# FSWSJE2IZ6BVKJ2.net
KiCad netlist of a schematic drawn in EAGLE
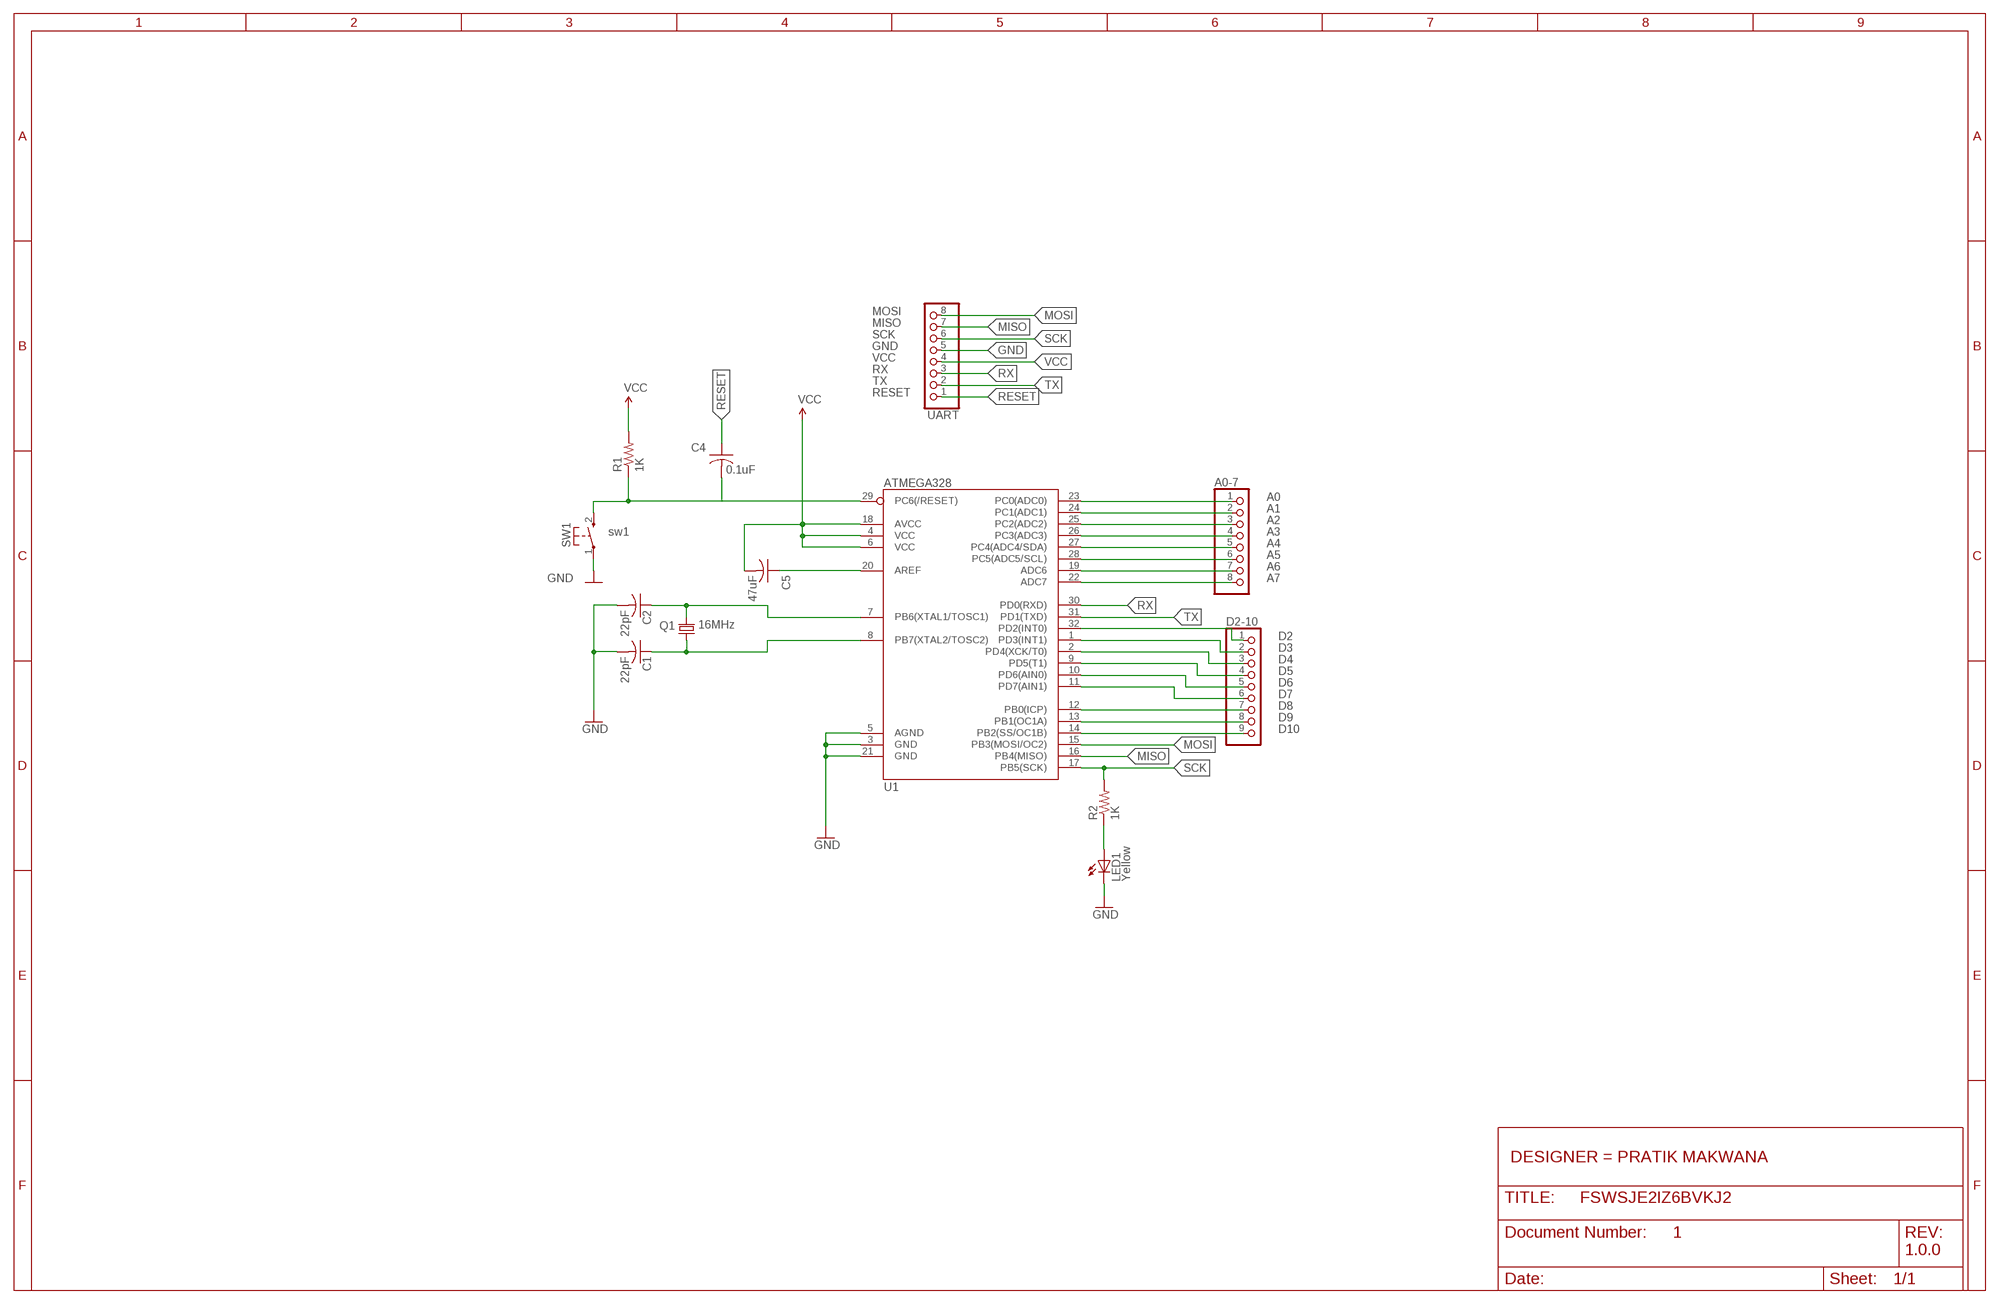
[diagram p0: schematic, sheet 1]

(export (version "E")
  (design (tool "Eeschema 10.0.6"))
  (components
    (comp (ref "A0-7")
      (value "PINHD-1X8CLEANBIG")
      (footprint "eagle-import:1X08-CLEANBIG")
      (libsource (lib "eagle-import") (part "PINHD-1X8CLEANBIG"))
    )
    (comp (ref "C1")
      (value "22pF")
      (footprint "eagle-import:C1206")
      (libsource (lib "eagle-import") (part "C-USC1206"))
    )
    (comp (ref "C2")
      (value "22pF")
      (footprint "eagle-import:C1206")
      (libsource (lib "eagle-import") (part "C-USC1206"))
    )
    (comp (ref "C4")
      (value "0.1uF")
      (footprint "eagle-import:C0805")
      (libsource (lib "eagle-import") (part "C-USC0805"))
    )
    (comp (ref "C5")
      (value "47uF")
      (footprint "eagle-import:C0805")
      (libsource (lib "eagle-import") (part "C-USC0805"))
    )
    (comp (ref "D2-10")
      (value "PINHD-1X9")
      (footprint "eagle-import:1X09-BIG")
      (libsource (lib "eagle-import") (part "PINHD-1X9"))
    )
    (comp (ref "LED1")
      (value "Yellow")
      (footprint "eagle-import:CHIP-LED0805")
      (libsource (lib "eagle-import") (part "LEDCHIP-LED0805"))
    )
    (comp (ref "Q1")
      (value "16MHz")
      (footprint "eagle-import:HC49_S")
      (libsource (lib "eagle-import") (part "CRYTALHC49S"))
    )
    (comp (ref "R1")
      (value "1K")
      (footprint "eagle-import:R1206")
      (libsource (lib "eagle-import") (part "R-US_R1206"))
    )
    (comp (ref "R2")
      (value "1K")
      (footprint "eagle-import:R1206")
      (libsource (lib "eagle-import") (part "R-US_R1206"))
    )
    (comp (ref "SW1")
      (value "sw1")
      (footprint "eagle-import:KSS-2EG4430")
      (libsource (lib "eagle-import") (part "KSS-2EG4430"))
    )
    (comp (ref "U1")
      (value "ATMEGA328")
      (footprint "eagle-import:TQFP32-08")
      (libsource (lib "eagle-import") (part "ATMEGA328"))
    )
    (comp (ref "UART")
      (value "PINHD-1X8CLEANBIG")
      (footprint "eagle-import:1X08-CLEANBIG")
      (libsource (lib "eagle-import") (part "PINHD-1X8CLEANBIG"))
    )
  )
  (nets
    (net (code "1") (name "/A0") (class "Default")
      (node (ref "A0-7") (pin "1") (pinfunction "1_1") (pintype "passive"))
      (node (ref "U1") (pin "23") (pinfunction "PC0(ADC0)_23") (pintype "bidirectional"))
    )
    (net (code "2") (name "/A1") (class "Default")
      (node (ref "A0-7") (pin "2") (pinfunction "2_2") (pintype "passive"))
      (node (ref "U1") (pin "24") (pinfunction "PC1(ADC1)_24") (pintype "bidirectional"))
    )
    (net (code "3") (name "/A2") (class "Default")
      (node (ref "A0-7") (pin "3") (pinfunction "3_3") (pintype "passive"))
      (node (ref "U1") (pin "25") (pinfunction "PC2(ADC2)_25") (pintype "bidirectional"))
    )
    (net (code "4") (name "/A3") (class "Default")
      (node (ref "A0-7") (pin "4") (pinfunction "4_4") (pintype "passive"))
      (node (ref "U1") (pin "26") (pinfunction "PC3(ADC3)_26") (pintype "bidirectional"))
    )
    (net (code "5") (name "/A4") (class "Default")
      (node (ref "A0-7") (pin "5") (pinfunction "5_5") (pintype "passive"))
      (node (ref "U1") (pin "27") (pinfunction "PC4(ADC4/SDA)_27") (pintype "bidirectional"))
    )
    (net (code "6") (name "/A5") (class "Default")
      (node (ref "A0-7") (pin "6") (pinfunction "6_6") (pintype "passive"))
      (node (ref "U1") (pin "28") (pinfunction "PC5(ADC5/SCL)_28") (pintype "bidirectional"))
    )
    (net (code "7") (name "/A6") (class "Default")
      (node (ref "A0-7") (pin "7") (pinfunction "7_7") (pintype "passive"))
      (node (ref "U1") (pin "19") (pinfunction "ADC6_19") (pintype "bidirectional"))
    )
    (net (code "8") (name "/A7") (class "Default")
      (node (ref "A0-7") (pin "8") (pinfunction "8_8") (pintype "passive"))
      (node (ref "U1") (pin "22") (pinfunction "ADC7_22") (pintype "bidirectional"))
    )
    (net (code "9") (name "/D2") (class "Default")
      (node (ref "D2-10") (pin "1") (pinfunction "1_1") (pintype "passive"))
      (node (ref "U1") (pin "32") (pinfunction "PD2(INT0)_32") (pintype "bidirectional"))
    )
    (net (code "10") (name "/D3") (class "Default")
      (node (ref "D2-10") (pin "2") (pinfunction "2_2") (pintype "passive"))
      (node (ref "U1") (pin "1") (pinfunction "PD3(INT1)_1") (pintype "bidirectional"))
    )
    (net (code "11") (name "/D4") (class "Default")
      (node (ref "D2-10") (pin "3") (pinfunction "3_3") (pintype "passive"))
      (node (ref "U1") (pin "2") (pinfunction "PD4(XCK/T0)_2") (pintype "bidirectional"))
    )
    (net (code "12") (name "/D5") (class "Default")
      (node (ref "D2-10") (pin "4") (pinfunction "4_4") (pintype "passive"))
      (node (ref "U1") (pin "9") (pinfunction "PD5(T1)_9") (pintype "bidirectional"))
    )
    (net (code "13") (name "/D6") (class "Default")
      (node (ref "D2-10") (pin "5") (pinfunction "5_5") (pintype "passive"))
      (node (ref "U1") (pin "10") (pinfunction "PD6(AIN0)_10") (pintype "bidirectional"))
    )
    (net (code "14") (name "/D7") (class "Default")
      (node (ref "D2-10") (pin "6") (pinfunction "6_6") (pintype "passive"))
      (node (ref "U1") (pin "11") (pinfunction "PD7(AIN1)_11") (pintype "bidirectional"))
    )
    (net (code "15") (name "/D8") (class "Default")
      (node (ref "D2-10") (pin "7") (pinfunction "7_7") (pintype "passive"))
      (node (ref "U1") (pin "12") (pinfunction "PB0(ICP)_12") (pintype "bidirectional"))
    )
    (net (code "16") (name "/D9") (class "Default")
      (node (ref "D2-10") (pin "8") (pinfunction "8_8") (pintype "passive"))
      (node (ref "U1") (pin "13") (pinfunction "PB1(OC1A)_13") (pintype "bidirectional"))
    )
    (net (code "17") (name "/D10") (class "Default")
      (node (ref "D2-10") (pin "9") (pinfunction "9_9") (pintype "passive"))
      (node (ref "U1") (pin "14") (pinfunction "PB2(SS/OC1B)_14") (pintype "bidirectional"))
    )
    (net (code "18") (name "/RST") (class "Default")
      (node (ref "C4") (pin "2") (pinfunction "2_2") (pintype "passive"))
      (node (ref "R1") (pin "1") (pinfunction "1_1") (pintype "passive"))
      (node (ref "SW1") (pin "2") (pinfunction "S_2") (pintype "passive"))
      (node (ref "U1") (pin "29") (pinfunction "PC6(/RESET)_29") (pintype "bidirectional"))
    )
    (net (code "19") (name "GND") (class "Default")
      (node (ref "C1") (pin "2") (pinfunction "2_2") (pintype "passive"))
      (node (ref "C2") (pin "2") (pinfunction "2_2") (pintype "passive"))
      (node (ref "LED1") (pin "C") (pinfunction "C_C") (pintype "passive"))
      (node (ref "SW1") (pin "1") (pinfunction "P_1") (pintype "passive"))
      (node (ref "U1") (pin "21") (pinfunction "GND_21") (pintype "bidirectional"))
      (node (ref "U1") (pin "3") (pinfunction "GND_3") (pintype "bidirectional"))
      (node (ref "U1") (pin "5") (pinfunction "AGND_5") (pintype "bidirectional"))
      (node (ref "UART") (pin "5") (pinfunction "5_5") (pintype "passive"))
    )
    (net (code "20") (name "MISO") (class "Default")
      (node (ref "U1") (pin "16") (pinfunction "PB4(MISO)_16") (pintype "bidirectional"))
      (node (ref "UART") (pin "7") (pinfunction "7_7") (pintype "passive"))
    )
    (net (code "21") (name "MOSI") (class "Default")
      (node (ref "U1") (pin "15") (pinfunction "PB3(MOSI/OC2)_15") (pintype "bidirectional"))
      (node (ref "UART") (pin "8") (pinfunction "8_8") (pintype "passive"))
    )
    (net (code "22") (name "Net-(LED1-PadA)") (class "Default")
      (node (ref "LED1") (pin "A") (pinfunction "A_A") (pintype "passive"))
      (node (ref "R2") (pin "1") (pinfunction "1_1") (pintype "passive"))
    )
    (net (code "23") (name "Net-(U1-AREF)") (class "Default")
      (node (ref "C5") (pin "1") (pinfunction "1_1") (pintype "passive"))
      (node (ref "U1") (pin "20") (pinfunction "AREF_20") (pintype "bidirectional"))
    )
    (net (code "24") (name "Net-(U1-PB6(XTAL1{slash}TOSC1))") (class "Default")
      (node (ref "C2") (pin "1") (pinfunction "1_1") (pintype "passive"))
      (node (ref "Q1") (pin "2") (pinfunction "2_2") (pintype "passive"))
      (node (ref "U1") (pin "7") (pinfunction "PB6(XTAL1/TOSC1)_7") (pintype "bidirectional"))
    )
    (net (code "25") (name "Net-(U1-PB7(XTAL2{slash}TOSC2))") (class "Default")
      (node (ref "C1") (pin "1") (pinfunction "1_1") (pintype "passive"))
      (node (ref "Q1") (pin "1") (pinfunction "1_1") (pintype "passive"))
      (node (ref "U1") (pin "8") (pinfunction "PB7(XTAL2/TOSC2)_8") (pintype "bidirectional"))
    )
    (net (code "26") (name "RESET") (class "Default")
      (node (ref "C4") (pin "1") (pinfunction "1_1") (pintype "passive"))
      (node (ref "UART") (pin "1") (pinfunction "1_1") (pintype "passive"))
    )
    (net (code "27") (name "RX") (class "Default")
      (node (ref "U1") (pin "30") (pinfunction "PD0(RXD)_30") (pintype "bidirectional"))
      (node (ref "UART") (pin "3") (pinfunction "3_3") (pintype "passive"))
    )
    (net (code "28") (name "SCK") (class "Default")
      (node (ref "R2") (pin "2") (pinfunction "2_2") (pintype "passive"))
      (node (ref "U1") (pin "17") (pinfunction "PB5(SCK)_17") (pintype "bidirectional"))
      (node (ref "UART") (pin "6") (pinfunction "6_6") (pintype "passive"))
    )
    (net (code "29") (name "TX") (class "Default")
      (node (ref "U1") (pin "31") (pinfunction "PD1(TXD)_31") (pintype "bidirectional"))
      (node (ref "UART") (pin "2") (pinfunction "2_2") (pintype "passive"))
    )
    (net (code "30") (name "VCC") (class "Default")
      (node (ref "C5") (pin "2") (pinfunction "2_2") (pintype "passive"))
      (node (ref "R1") (pin "2") (pinfunction "2_2") (pintype "passive"))
      (node (ref "U1") (pin "18") (pinfunction "AVCC_18") (pintype "bidirectional"))
      (node (ref "U1") (pin "4") (pinfunction "VCC_4") (pintype "bidirectional"))
      (node (ref "U1") (pin "6") (pinfunction "VCC_6") (pintype "bidirectional"))
      (node (ref "UART") (pin "4") (pinfunction "4_4") (pintype "passive"))
    )
  )
)
